# design_1_-_fan_controller.net
KiCad netlist of a schematic drawn in EAGLE
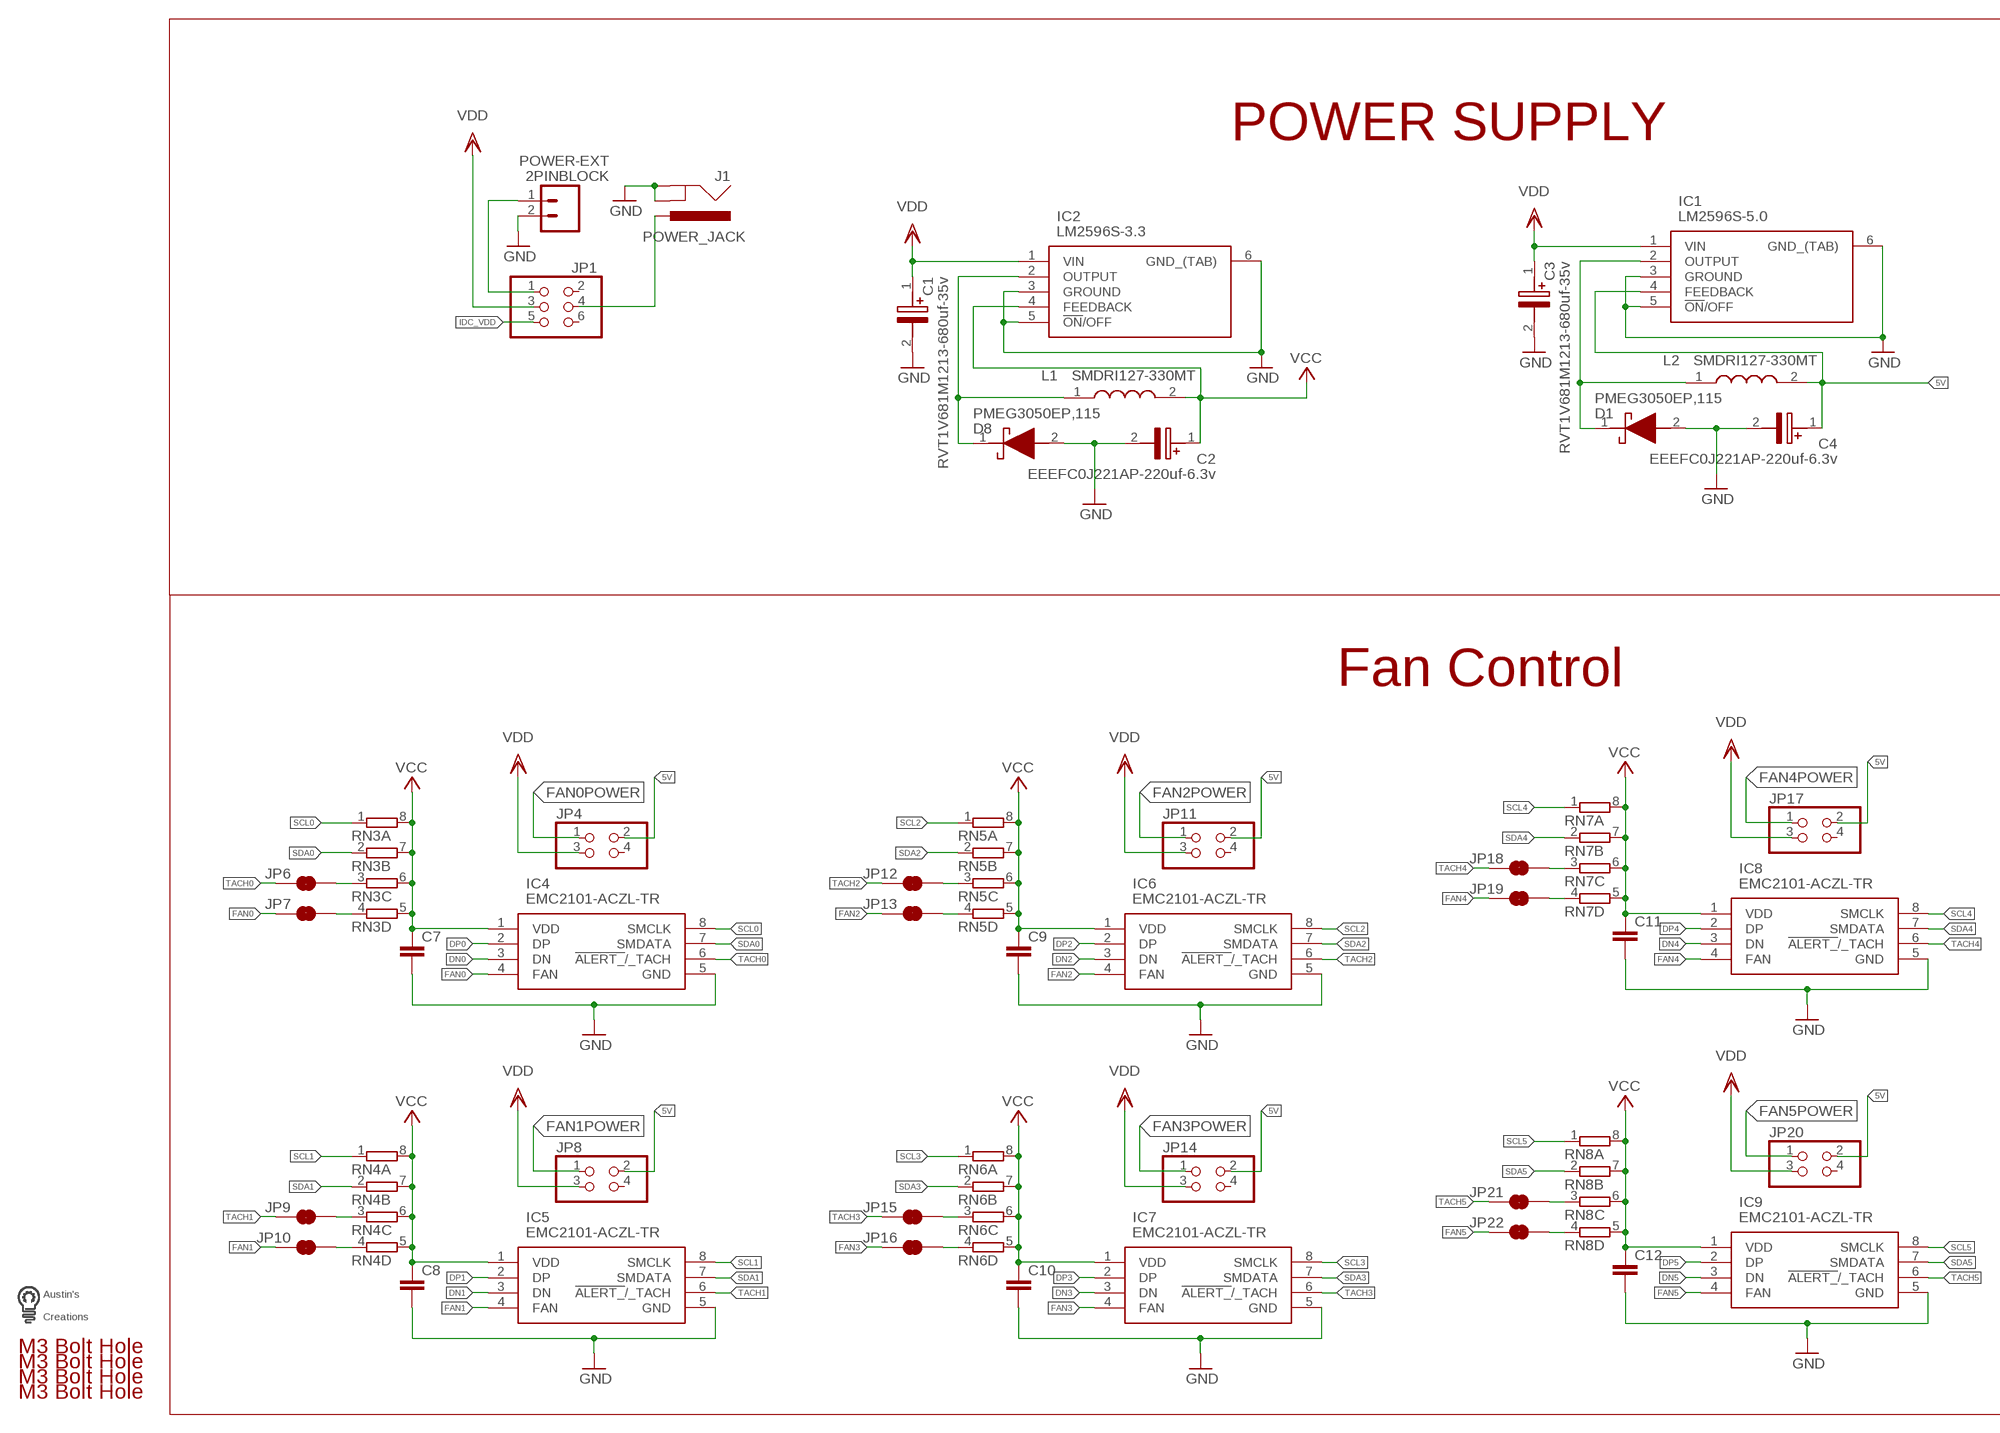
[diagram p0: schematic, sheet 1, part 1 of 2]
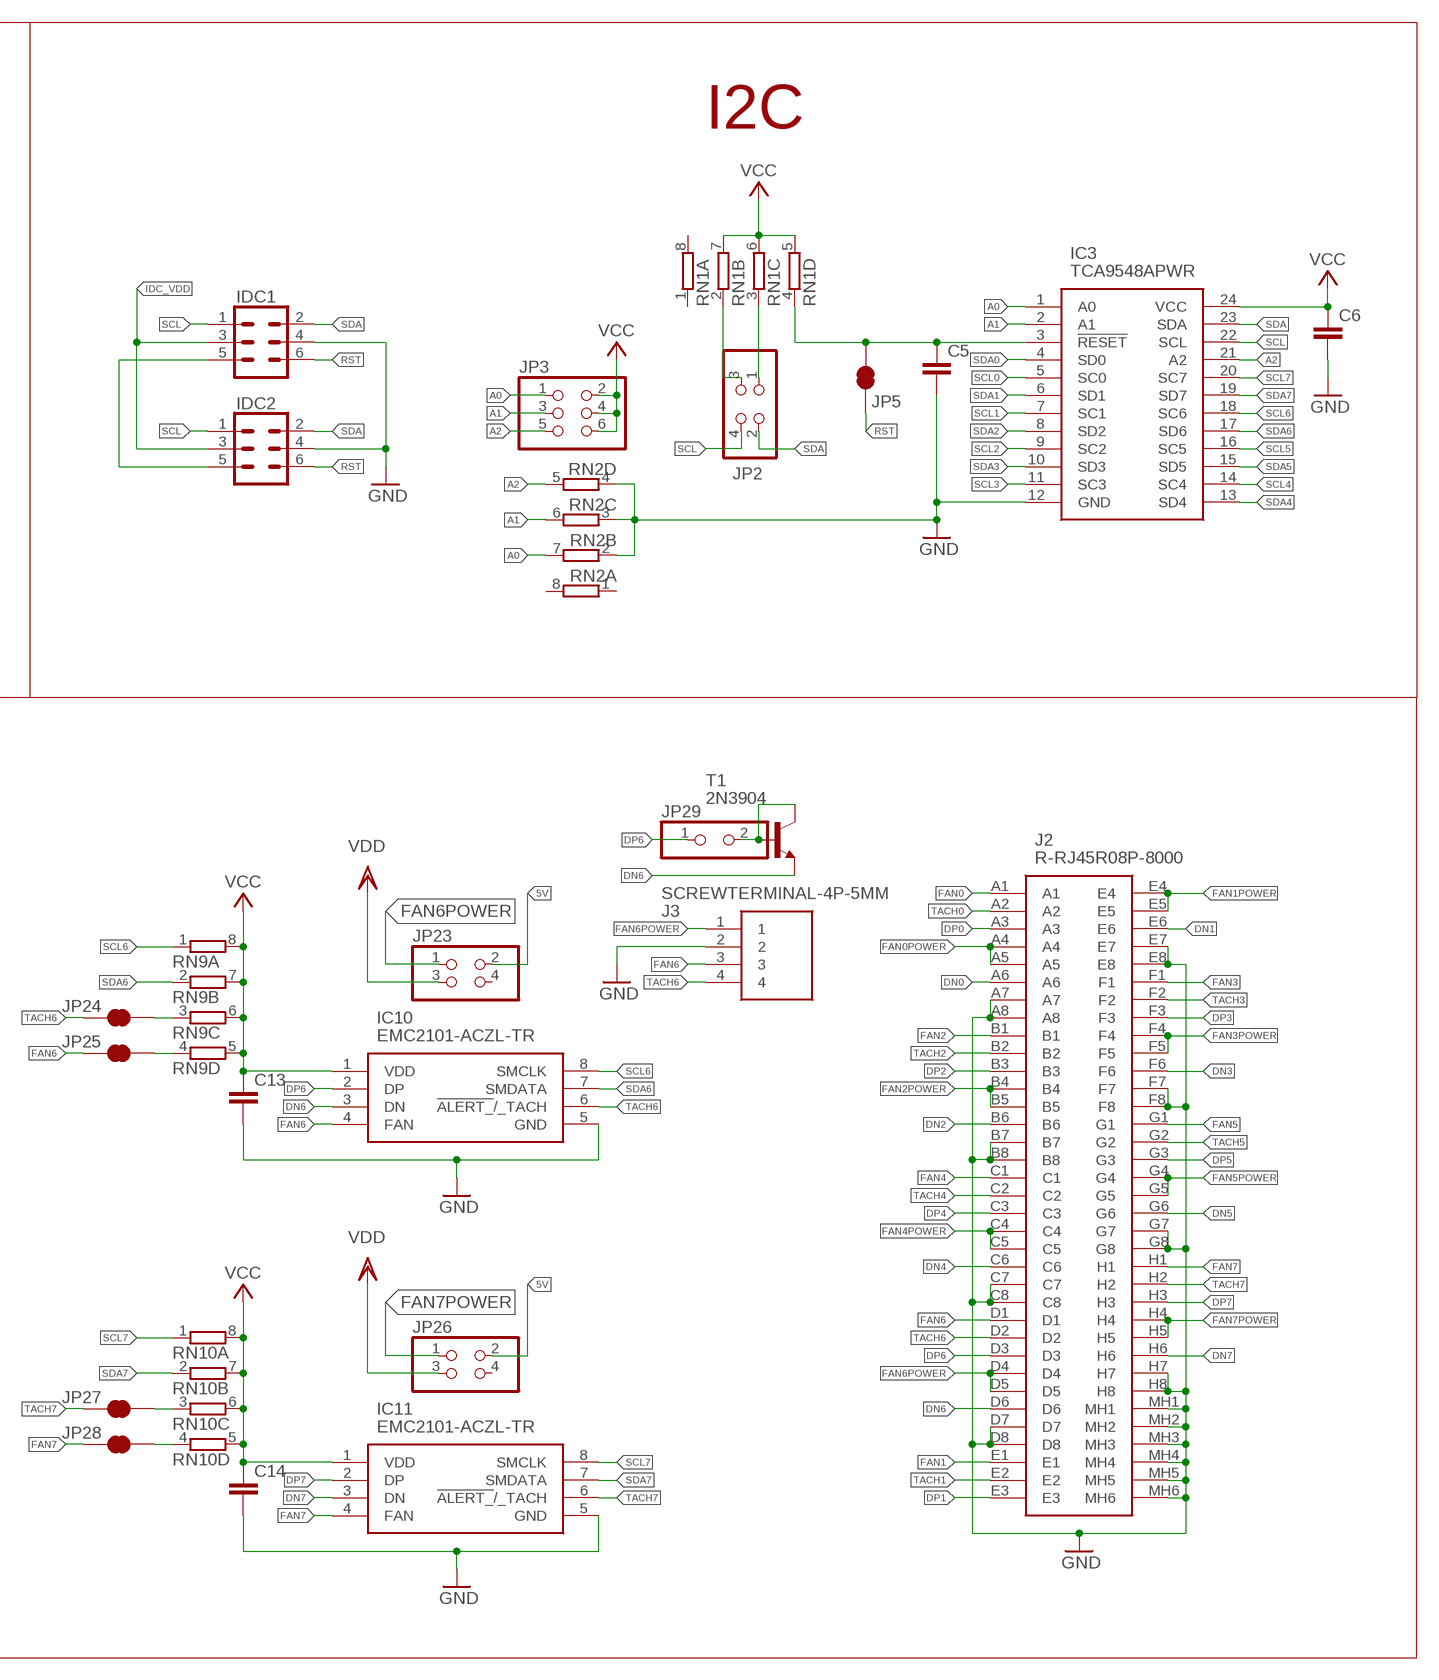
[diagram p1: schematic, sheet 1, part 2 of 2]

(export (version "E")
  (design (tool "Eeschema 10.0.6"))
  (components
    (comp (ref "C1")
      (value "RVT1V681M1213-680uf-35v")
      (footprint "eagle-import:CAPAE1350X1400N")
      (fields
        (field (name "MANUFACTURER_PART_NUMBER") "EEE-HD1V681AQ")
        (field (name "MOUSER_PART_NUMBER") "667-EEE-HD1V681AQ")
      )
      (libsource (lib "eagle-import") (part "EEE-HD1V681AQ"))
    )
    (comp (ref "C2")
      (value "EEEFC0J221AP-220uf-6.3v")
      (footprint "eagle-import:CAPAE830X650N")
      (fields (field (name "MANUFACTURER_PART_NUMBER") "EEEFC0J221AP"))
      (libsource (lib "eagle-import") (part "EEEFC0J221AP"))
    )
    (comp (ref "C3")
      (value "RVT1V681M1213-680uf-35v")
      (footprint "eagle-import:CAPAE1350X1400N")
      (fields
        (field (name "MANUFACTURER_PART_NUMBER") "EEE-HD1V681AQ")
        (field (name "MOUSER_PART_NUMBER") "667-EEE-HD1V681AQ")
      )
      (libsource (lib "eagle-import") (part "EEE-HD1V681AQ"))
    )
    (comp (ref "C4")
      (value "EEEFC0J221AP-220uf-6.3v")
      (footprint "eagle-import:CAPAE830X650N")
      (fields (field (name "MANUFACTURER_PART_NUMBER") "EEEFC0J221AP"))
      (libsource (lib "eagle-import") (part "EEEFC0J221AP"))
    )
    (comp (ref "C5")
      (value "C-EUC0603")
      (footprint "eagle-import:C0603")
      (libsource (lib "eagle-import") (part "C-EUC0603"))
    )
    (comp (ref "C6")
      (value "C-EUC0603")
      (footprint "eagle-import:C0603")
      (libsource (lib "eagle-import") (part "C-EUC0603"))
    )
    (comp (ref "C7")
      (value "C-EUC0603")
      (footprint "eagle-import:C0603")
      (libsource (lib "eagle-import") (part "C-EUC0603"))
    )
    (comp (ref "C8")
      (value "C-EUC0603")
      (footprint "eagle-import:C0603")
      (libsource (lib "eagle-import") (part "C-EUC0603"))
    )
    (comp (ref "C9")
      (value "C-EUC0603")
      (footprint "eagle-import:C0603")
      (libsource (lib "eagle-import") (part "C-EUC0603"))
    )
    (comp (ref "C10")
      (value "C-EUC0603")
      (footprint "eagle-import:C0603")
      (libsource (lib "eagle-import") (part "C-EUC0603"))
    )
    (comp (ref "C11")
      (value "C-EUC0603")
      (footprint "eagle-import:C0603")
      (libsource (lib "eagle-import") (part "C-EUC0603"))
    )
    (comp (ref "C12")
      (value "C-EUC0603")
      (footprint "eagle-import:C0603")
      (libsource (lib "eagle-import") (part "C-EUC0603"))
    )
    (comp (ref "C13")
      (value "C-EUC0603")
      (footprint "eagle-import:C0603")
      (libsource (lib "eagle-import") (part "C-EUC0603"))
    )
    (comp (ref "C14")
      (value "C-EUC0603")
      (footprint "eagle-import:C0603")
      (libsource (lib "eagle-import") (part "C-EUC0603"))
    )
    (comp (ref "D1")
      (value "PMEG3050EP,115")
      (footprint "eagle-import:PMEG3050EP115")
      (fields (field (name "MOUSER_PART_NUMBER") "771-PMEG3050EP115"))
      (libsource (lib "eagle-import") (part "PMEG3050EP,115"))
    )
    (comp (ref "D8")
      (value "PMEG3050EP,115")
      (footprint "eagle-import:PMEG3050EP115")
      (fields (field (name "MOUSER_PART_NUMBER") "771-PMEG3050EP115"))
      (libsource (lib "eagle-import") (part "PMEG3050EP,115"))
    )
    (comp (ref "IC1")
      (value "LM2596S-5.0")
      (footprint "eagle-import:TO170P1435X465-6N")
      (fields
        (field (name "MANUFACTURER_PART_NUMBER") "LM2596S-3.3/NOPB")
        (field (name "MOUSER_PART_NUMBER") "926-LM2596S-3.3/NOPB")
      )
      (libsource (lib "eagle-import") (part "LM2596S-3.3_NOPB"))
    )
    (comp (ref "IC2")
      (value "LM2596S-3.3")
      (footprint "eagle-import:TO170P1435X465-6N")
      (fields
        (field (name "MANUFACTURER_PART_NUMBER") "LM2596S-3.3/NOPB")
        (field (name "MOUSER_PART_NUMBER") "926-LM2596S-3.3/NOPB")
      )
      (libsource (lib "eagle-import") (part "LM2596S-3.3_NOPB"))
    )
    (comp (ref "IC3")
      (value "TCA9548APWR")
      (footprint "eagle-import:SOP65P640X120-24N")
      (fields (field (name "MOUSER_PART_NUMBER") "595-TCA9548APWR"))
      (libsource (lib "eagle-import") (part "TCA9548APWR"))
    )
    (comp (ref "IC4")
      (value "EMC2101-ACZL-TR")
      (footprint "eagle-import:SOP65P490X110-8N")
      (fields (field (name "MOUSER_PART_NUMBER") "886-EMC2101-ACZL-TR"))
      (libsource (lib "eagle-import") (part "EMC2101-ACZL-TR"))
    )
    (comp (ref "IC5")
      (value "EMC2101-ACZL-TR")
      (footprint "eagle-import:SOP65P490X110-8N")
      (fields (field (name "MOUSER_PART_NUMBER") "886-EMC2101-ACZL-TR"))
      (libsource (lib "eagle-import") (part "EMC2101-ACZL-TR"))
    )
    (comp (ref "IC6")
      (value "EMC2101-ACZL-TR")
      (footprint "eagle-import:SOP65P490X110-8N")
      (fields (field (name "MOUSER_PART_NUMBER") "886-EMC2101-ACZL-TR"))
      (libsource (lib "eagle-import") (part "EMC2101-ACZL-TR"))
    )
    (comp (ref "IC7")
      (value "EMC2101-ACZL-TR")
      (footprint "eagle-import:SOP65P490X110-8N")
      (fields (field (name "MOUSER_PART_NUMBER") "886-EMC2101-ACZL-TR"))
      (libsource (lib "eagle-import") (part "EMC2101-ACZL-TR"))
    )
    (comp (ref "IC8")
      (value "EMC2101-ACZL-TR")
      (footprint "eagle-import:SOP65P490X110-8N")
      (fields (field (name "MOUSER_PART_NUMBER") "886-EMC2101-ACZL-TR"))
      (libsource (lib "eagle-import") (part "EMC2101-ACZL-TR"))
    )
    (comp (ref "IC9")
      (value "EMC2101-ACZL-TR")
      (footprint "eagle-import:SOP65P490X110-8N")
      (fields (field (name "MOUSER_PART_NUMBER") "886-EMC2101-ACZL-TR"))
      (libsource (lib "eagle-import") (part "EMC2101-ACZL-TR"))
    )
    (comp (ref "IC10")
      (value "EMC2101-ACZL-TR")
      (footprint "eagle-import:SOP65P490X110-8N")
      (fields (field (name "MOUSER_PART_NUMBER") "886-EMC2101-ACZL-TR"))
      (libsource (lib "eagle-import") (part "EMC2101-ACZL-TR"))
    )
    (comp (ref "IC11")
      (value "EMC2101-ACZL-TR")
      (footprint "eagle-import:SOP65P490X110-8N")
      (fields (field (name "MOUSER_PART_NUMBER") "886-EMC2101-ACZL-TR"))
      (libsource (lib "eagle-import") (part "EMC2101-ACZL-TR"))
    )
    (comp (ref "IDC1")
      (value "CONN_03X2SHROUD")
      (footprint "eagle-import:2X3-SHROUDED")
      (libsource (lib "eagle-import") (part "CONN_03X2SHROUD"))
    )
    (comp (ref "IDC2")
      (value "CONN_03X2SHROUD")
      (footprint "eagle-import:2X3-SHROUDED")
      (libsource (lib "eagle-import") (part "CONN_03X2SHROUD"))
    )
    (comp (ref "J1")
      (value "POWER_JACK")
      (footprint "eagle-import:POWER_JACK_PTH")
      (libsource (lib "eagle-import") (part "POWER_JACK"))
    )
    (comp (ref "J2")
      (value "R-RJ45R08P-8000")
      (footprint "eagle-import:RRJ45R08P8000")
      (libsource (lib "eagle-import") (part "R-RJ45R08P-8000"))
    )
    (comp (ref "J3")
      (value "SCREWTERMINAL-4P-5MM")
      (footprint "eagle-import:SCREWTERMINAL-4P-5MM")
      (fields
        (field (name "MANUFACTURER_PART_NUMBER") "TB001-500-04BE")
        (field (name "MOUSER_PART_NUMBER") "490-TB001-500-04BE")
      )
      (libsource (lib "eagle-import") (part "SCREWTERMINAL-4P-5MM"))
    )
    (comp (ref "JP1")
      (value "PINHD-2X3")
      (footprint "eagle-import:2X03")
      (libsource (lib "eagle-import") (part "PINHD-2X3"))
    )
    (comp (ref "JP2")
      (value "PINHD-2X2")
      (footprint "eagle-import:2X02")
      (libsource (lib "eagle-import") (part "PINHD-2X2"))
    )
    (comp (ref "JP3")
      (value "PINHD-2X3")
      (footprint "eagle-import:2X03")
      (libsource (lib "eagle-import") (part "PINHD-2X3"))
    )
    (comp (ref "JP4")
      (value "PINHD-2X2")
      (footprint "eagle-import:2X02")
      (libsource (lib "eagle-import") (part "PINHD-2X2"))
    )
    (comp (ref "JP5")
      (value "JUMPER-SMT_2_NC_TRACE_SILK")
      (footprint "eagle-import:SMT-JUMPER_2_NC_TRACE_SILK")
      (libsource (lib "eagle-import") (part "JUMPER-SMT_2_NC_TRACE_SILK"))
    )
    (comp (ref "JP6")
      (value "JUMPER-SMT_2_NC_TRACE_SILK")
      (footprint "eagle-import:SMT-JUMPER_2_NC_TRACE_SILK")
      (libsource (lib "eagle-import") (part "JUMPER-SMT_2_NC_TRACE_SILK"))
    )
    (comp (ref "JP7")
      (value "JUMPER-SMT_2_NC_TRACE_SILK")
      (footprint "eagle-import:SMT-JUMPER_2_NC_TRACE_SILK")
      (libsource (lib "eagle-import") (part "JUMPER-SMT_2_NC_TRACE_SILK"))
    )
    (comp (ref "JP8")
      (value "PINHD-2X2")
      (footprint "eagle-import:2X02")
      (libsource (lib "eagle-import") (part "PINHD-2X2"))
    )
    (comp (ref "JP9")
      (value "JUMPER-SMT_2_NC_TRACE_SILK")
      (footprint "eagle-import:SMT-JUMPER_2_NC_TRACE_SILK")
      (libsource (lib "eagle-import") (part "JUMPER-SMT_2_NC_TRACE_SILK"))
    )
    (comp (ref "JP10")
      (value "JUMPER-SMT_2_NC_TRACE_SILK")
      (footprint "eagle-import:SMT-JUMPER_2_NC_TRACE_SILK")
      (libsource (lib "eagle-import") (part "JUMPER-SMT_2_NC_TRACE_SILK"))
    )
    (comp (ref "JP11")
      (value "PINHD-2X2")
      (footprint "eagle-import:2X02")
      (libsource (lib "eagle-import") (part "PINHD-2X2"))
    )
    (comp (ref "JP12")
      (value "JUMPER-SMT_2_NC_TRACE_SILK")
      (footprint "eagle-import:SMT-JUMPER_2_NC_TRACE_SILK")
      (libsource (lib "eagle-import") (part "JUMPER-SMT_2_NC_TRACE_SILK"))
    )
    (comp (ref "JP13")
      (value "JUMPER-SMT_2_NC_TRACE_SILK")
      (footprint "eagle-import:SMT-JUMPER_2_NC_TRACE_SILK")
      (libsource (lib "eagle-import") (part "JUMPER-SMT_2_NC_TRACE_SILK"))
    )
    (comp (ref "JP14")
      (value "PINHD-2X2")
      (footprint "eagle-import:2X02")
      (libsource (lib "eagle-import") (part "PINHD-2X2"))
    )
    (comp (ref "JP15")
      (value "JUMPER-SMT_2_NC_TRACE_SILK")
      (footprint "eagle-import:SMT-JUMPER_2_NC_TRACE_SILK")
      (libsource (lib "eagle-import") (part "JUMPER-SMT_2_NC_TRACE_SILK"))
    )
    (comp (ref "JP16")
      (value "JUMPER-SMT_2_NC_TRACE_SILK")
      (footprint "eagle-import:SMT-JUMPER_2_NC_TRACE_SILK")
      (libsource (lib "eagle-import") (part "JUMPER-SMT_2_NC_TRACE_SILK"))
    )
    (comp (ref "JP17")
      (value "PINHD-2X2")
      (footprint "eagle-import:2X02")
      (libsource (lib "eagle-import") (part "PINHD-2X2"))
    )
    (comp (ref "JP18")
      (value "JUMPER-SMT_2_NC_TRACE_SILK")
      (footprint "eagle-import:SMT-JUMPER_2_NC_TRACE_SILK")
      (libsource (lib "eagle-import") (part "JUMPER-SMT_2_NC_TRACE_SILK"))
    )
    (comp (ref "JP19")
      (value "JUMPER-SMT_2_NC_TRACE_SILK")
      (footprint "eagle-import:SMT-JUMPER_2_NC_TRACE_SILK")
      (libsource (lib "eagle-import") (part "JUMPER-SMT_2_NC_TRACE_SILK"))
    )
    (comp (ref "JP20")
      (value "PINHD-2X2")
      (footprint "eagle-import:2X02")
      (libsource (lib "eagle-import") (part "PINHD-2X2"))
    )
    (comp (ref "JP21")
      (value "JUMPER-SMT_2_NC_TRACE_SILK")
      (footprint "eagle-import:SMT-JUMPER_2_NC_TRACE_SILK")
      (libsource (lib "eagle-import") (part "JUMPER-SMT_2_NC_TRACE_SILK"))
    )
    (comp (ref "JP22")
      (value "JUMPER-SMT_2_NC_TRACE_SILK")
      (footprint "eagle-import:SMT-JUMPER_2_NC_TRACE_SILK")
      (libsource (lib "eagle-import") (part "JUMPER-SMT_2_NC_TRACE_SILK"))
    )
    (comp (ref "JP23")
      (value "PINHD-2X2")
      (footprint "eagle-import:2X02")
      (libsource (lib "eagle-import") (part "PINHD-2X2"))
    )
    (comp (ref "JP24")
      (value "JUMPER-SMT_2_NC_TRACE_SILK")
      (footprint "eagle-import:SMT-JUMPER_2_NC_TRACE_SILK")
      (libsource (lib "eagle-import") (part "JUMPER-SMT_2_NC_TRACE_SILK"))
    )
    (comp (ref "JP25")
      (value "JUMPER-SMT_2_NC_TRACE_SILK")
      (footprint "eagle-import:SMT-JUMPER_2_NC_TRACE_SILK")
      (libsource (lib "eagle-import") (part "JUMPER-SMT_2_NC_TRACE_SILK"))
    )
    (comp (ref "JP26")
      (value "PINHD-2X2")
      (footprint "eagle-import:2X02")
      (libsource (lib "eagle-import") (part "PINHD-2X2"))
    )
    (comp (ref "JP27")
      (value "JUMPER-SMT_2_NC_TRACE_SILK")
      (footprint "eagle-import:SMT-JUMPER_2_NC_TRACE_SILK")
      (libsource (lib "eagle-import") (part "JUMPER-SMT_2_NC_TRACE_SILK"))
    )
    (comp (ref "JP28")
      (value "JUMPER-SMT_2_NC_TRACE_SILK")
      (footprint "eagle-import:SMT-JUMPER_2_NC_TRACE_SILK")
      (libsource (lib "eagle-import") (part "JUMPER-SMT_2_NC_TRACE_SILK"))
    )
    (comp (ref "JP29")
      (value "PINHD-1X2")
      (footprint "eagle-import:1X02")
      (libsource (lib "eagle-import") (part "PINHD-1X2"))
    )
    (comp (ref "L1")
      (value "SMDRI127-330MT")
      (footprint "eagle-import:INDPM120120X800N")
      (fields
        (field (name "MANUFACTURER_PART_NUMBER") "CDRH127/LDNP-330MC")
        (field (name "MOUSER_PART_NUMBER") "851-CDRH127LDNP330MC")
      )
      (libsource (lib "eagle-import") (part "CDRH127_LDNP-330MC"))
    )
    (comp (ref "L2")
      (value "SMDRI127-330MT")
      (footprint "eagle-import:INDPM120120X800N")
      (fields
        (field (name "MANUFACTURER_PART_NUMBER") "CDRH127/LDNP-330MC")
        (field (name "MOUSER_PART_NUMBER") "851-CDRH127LDNP330MC")
      )
      (libsource (lib "eagle-import") (part "CDRH127_LDNP-330MC"))
    )
    (comp (ref "POWER-EXT")
      (value "2PINBLOCK")
      (footprint "eagle-import:SCREWTERMINAL-5MM-2")
      (libsource (lib "eagle-import") (part "2PINBLOCK"))
    )
    (comp (ref "RN1")
      (value "4R-N0603-ARC")
      (footprint "eagle-import:0603-ARC")
      (libsource (lib "eagle-import") (part "4R-N0603-ARC"))
    )
    (comp (ref "RN2")
      (value "4R-N0603-ARC")
      (footprint "eagle-import:0603-ARC")
      (libsource (lib "eagle-import") (part "4R-N0603-ARC"))
    )
    (comp (ref "RN3")
      (value "4R-N0603-ARC")
      (footprint "eagle-import:0603-ARC")
      (libsource (lib "eagle-import") (part "4R-N0603-ARC"))
    )
    (comp (ref "RN4")
      (value "4R-N0603-ARC")
      (footprint "eagle-import:0603-ARC")
      (libsource (lib "eagle-import") (part "4R-N0603-ARC"))
    )
    (comp (ref "RN5")
      (value "4R-N0603-ARC")
      (footprint "eagle-import:0603-ARC")
      (libsource (lib "eagle-import") (part "4R-N0603-ARC"))
    )
    (comp (ref "RN6")
      (value "4R-N0603-ARC")
      (footprint "eagle-import:0603-ARC")
      (libsource (lib "eagle-import") (part "4R-N0603-ARC"))
    )
    (comp (ref "RN7")
      (value "4R-N0603-ARC")
      (footprint "eagle-import:0603-ARC")
      (libsource (lib "eagle-import") (part "4R-N0603-ARC"))
    )
    (comp (ref "RN8")
      (value "4R-N0603-ARC")
      (footprint "eagle-import:0603-ARC")
      (libsource (lib "eagle-import") (part "4R-N0603-ARC"))
    )
    (comp (ref "RN9")
      (value "4R-N0603-ARC")
      (footprint "eagle-import:0603-ARC")
      (libsource (lib "eagle-import") (part "4R-N0603-ARC"))
    )
    (comp (ref "RN10")
      (value "4R-N0603-ARC")
      (footprint "eagle-import:0603-ARC")
      (libsource (lib "eagle-import") (part "4R-N0603-ARC"))
    )
    (comp (ref "T1")
      (value "2N3904")
      (footprint "eagle-import:TO92")
      (libsource (lib "eagle-import") (part "2N3904"))
    )
    (comp (ref "U$1")
      (value "M3BOLTHOLE")
      (footprint "eagle-import:M3BOLTHOLE")
      (libsource (lib "eagle-import") (part "M3BOLTHOLE"))
    )
    (comp (ref "U$2")
      (value "M3BOLTHOLE")
      (footprint "eagle-import:M3BOLTHOLE")
      (libsource (lib "eagle-import") (part "M3BOLTHOLE"))
    )
    (comp (ref "U$3")
      (value "M3BOLTHOLE")
      (footprint "eagle-import:M3BOLTHOLE")
      (libsource (lib "eagle-import") (part "M3BOLTHOLE"))
    )
    (comp (ref "U$4")
      (value "M3BOLTHOLE")
      (footprint "eagle-import:M3BOLTHOLE")
      (libsource (lib "eagle-import") (part "M3BOLTHOLE"))
    )
    (comp (ref "U$5")
      (value "LOGOMED")
      (footprint "eagle-import:LOGOMED")
      (libsource (lib "eagle-import") (part "LOGOMED"))
    )
  )
  (nets
    (net (code "1") (name "5V") (class "Default")
      (node (ref "C4") (pin "1") (pinfunction "+_1") (pintype "bidirectional"))
      (node (ref "IC1") (pin "4") (pinfunction "FEEDBACK_4") (pintype "bidirectional"))
      (node (ref "JP11") (pin "2") (pinfunction "2_2") (pintype "passive"))
      (node (ref "JP14") (pin "2") (pinfunction "2_2") (pintype "passive"))
      (node (ref "JP17") (pin "2") (pinfunction "2_2") (pintype "passive"))
      (node (ref "JP20") (pin "2") (pinfunction "2_2") (pintype "passive"))
      (node (ref "JP23") (pin "2") (pinfunction "2_2") (pintype "passive"))
      (node (ref "JP26") (pin "2") (pinfunction "2_2") (pintype "passive"))
      (node (ref "JP4") (pin "2") (pinfunction "2_2") (pintype "passive"))
      (node (ref "JP8") (pin "2") (pinfunction "2_2") (pintype "passive"))
      (node (ref "L2") (pin "2") (pinfunction "2_2") (pintype "bidirectional"))
    )
    (net (code "2") (name "A0") (class "Default")
      (node (ref "IC3") (pin "1") (pinfunction "A0_1") (pintype "bidirectional"))
      (node (ref "JP3") (pin "1") (pinfunction "1_1") (pintype "passive"))
      (node (ref "RN2") (pin "7") (pinfunction "2_7") (pintype "passive"))
    )
    (net (code "3") (name "A1") (class "Default")
      (node (ref "IC3") (pin "2") (pinfunction "A1_2") (pintype "bidirectional"))
      (node (ref "JP3") (pin "3") (pinfunction "3_3") (pintype "passive"))
      (node (ref "RN2") (pin "6") (pinfunction "2_6") (pintype "passive"))
    )
    (net (code "4") (name "A2") (class "Default")
      (node (ref "IC3") (pin "21") (pinfunction "A2_21") (pintype "bidirectional"))
      (node (ref "JP3") (pin "5") (pinfunction "5_5") (pintype "passive"))
      (node (ref "RN2") (pin "5") (pinfunction "2_5") (pintype "passive"))
    )
    (net (code "5") (name "DN0") (class "Default")
      (node (ref "IC4") (pin "3") (pinfunction "DN_3") (pintype "input"))
      (node (ref "J2") (pin "A6") (pinfunction "A6_A6") (pintype "bidirectional"))
    )
    (net (code "6") (name "DN1") (class "Default")
      (node (ref "IC5") (pin "3") (pinfunction "DN_3") (pintype "input"))
      (node (ref "J2") (pin "E6") (pinfunction "E6_E6") (pintype "bidirectional"))
    )
    (net (code "7") (name "DN2") (class "Default")
      (node (ref "IC6") (pin "3") (pinfunction "DN_3") (pintype "input"))
      (node (ref "J2") (pin "B6") (pinfunction "B6_B6") (pintype "bidirectional"))
    )
    (net (code "8") (name "DN3") (class "Default")
      (node (ref "IC7") (pin "3") (pinfunction "DN_3") (pintype "input"))
      (node (ref "J2") (pin "F6") (pinfunction "F6_F6") (pintype "bidirectional"))
    )
    (net (code "9") (name "DN4") (class "Default")
      (node (ref "IC8") (pin "3") (pinfunction "DN_3") (pintype "input"))
      (node (ref "J2") (pin "C6") (pinfunction "C6_C6") (pintype "bidirectional"))
    )
    (net (code "10") (name "DN5") (class "Default")
      (node (ref "IC9") (pin "3") (pinfunction "DN_3") (pintype "input"))
      (node (ref "J2") (pin "G6") (pinfunction "G6_G6") (pintype "bidirectional"))
    )
    (net (code "11") (name "DN6") (class "Default")
      (node (ref "IC10") (pin "3") (pinfunction "DN_3") (pintype "input"))
      (node (ref "J2") (pin "D6") (pinfunction "D6_D6") (pintype "bidirectional"))
      (node (ref "T1") (pin "3") (pinfunction "E_3") (pintype "passive"))
    )
    (net (code "12") (name "DN7") (class "Default")
      (node (ref "IC11") (pin "3") (pinfunction "DN_3") (pintype "input"))
      (node (ref "J2") (pin "H6") (pinfunction "H6_H6") (pintype "bidirectional"))
    )
    (net (code "13") (name "DP0") (class "Default")
      (node (ref "IC4") (pin "2") (pinfunction "DP_2") (pintype "input"))
      (node (ref "J2") (pin "A3") (pinfunction "A3_A3") (pintype "bidirectional"))
    )
    (net (code "14") (name "DP1") (class "Default")
      (node (ref "IC5") (pin "2") (pinfunction "DP_2") (pintype "input"))
      (node (ref "J2") (pin "E3") (pinfunction "E3_E3") (pintype "bidirectional"))
    )
    (net (code "15") (name "DP2") (class "Default")
      (node (ref "IC6") (pin "2") (pinfunction "DP_2") (pintype "input"))
      (node (ref "J2") (pin "B3") (pinfunction "B3_B3") (pintype "bidirectional"))
    )
    (net (code "16") (name "DP3") (class "Default")
      (node (ref "IC7") (pin "2") (pinfunction "DP_2") (pintype "input"))
      (node (ref "J2") (pin "F3") (pinfunction "F3_F3") (pintype "bidirectional"))
    )
    (net (code "17") (name "DP4") (class "Default")
      (node (ref "IC8") (pin "2") (pinfunction "DP_2") (pintype "input"))
      (node (ref "J2") (pin "C3") (pinfunction "C3_C3") (pintype "bidirectional"))
    )
    (net (code "18") (name "DP5") (class "Default")
      (node (ref "IC9") (pin "2") (pinfunction "DP_2") (pintype "input"))
      (node (ref "J2") (pin "G3") (pinfunction "G3_G3") (pintype "bidirectional"))
    )
    (net (code "19") (name "DP6") (class "Default")
      (node (ref "IC10") (pin "2") (pinfunction "DP_2") (pintype "input"))
      (node (ref "J2") (pin "D3") (pinfunction "D3_D3") (pintype "bidirectional"))
      (node (ref "JP29") (pin "1") (pinfunction "1_1") (pintype "passive"))
    )
    (net (code "20") (name "DP7") (class "Default")
      (node (ref "IC11") (pin "2") (pinfunction "DP_2") (pintype "input"))
      (node (ref "J2") (pin "H3") (pinfunction "H3_H3") (pintype "bidirectional"))
    )
    (net (code "21") (name "FAN0") (class "Default")
      (node (ref "IC4") (pin "4") (pinfunction "FAN_4") (pintype "output"))
      (node (ref "J2") (pin "A1") (pinfunction "A1_A1") (pintype "bidirectional"))
      (node (ref "JP7") (pin "1") (pinfunction "1_1") (pintype "passive"))
    )
    (net (code "22") (name "FAN0POWER") (class "Default")
      (node (ref "J2") (pin "A4") (pinfunction "A4_A4") (pintype "bidirectional"))
      (node (ref "J2") (pin "A5") (pinfunction "A5_A5") (pintype "bidirectional"))
      (node (ref "JP4") (pin "1") (pinfunction "1_1") (pintype "passive"))
    )
    (net (code "23") (name "FAN1") (class "Default")
      (node (ref "IC5") (pin "4") (pinfunction "FAN_4") (pintype "output"))
      (node (ref "J2") (pin "E1") (pinfunction "E1_E1") (pintype "bidirectional"))
      (node (ref "JP10") (pin "1") (pinfunction "1_1") (pintype "passive"))
    )
    (net (code "24") (name "FAN1POWER") (class "Default")
      (node (ref "J2") (pin "E4") (pinfunction "E4_E4") (pintype "bidirectional"))
      (node (ref "J2") (pin "E5") (pinfunction "E5_E5") (pintype "bidirectional"))
      (node (ref "JP8") (pin "1") (pinfunction "1_1") (pintype "passive"))
    )
    (net (code "25") (name "FAN2") (class "Default")
      (node (ref "IC6") (pin "4") (pinfunction "FAN_4") (pintype "output"))
      (node (ref "J2") (pin "B1") (pinfunction "B1_B1") (pintype "bidirectional"))
      (node (ref "JP13") (pin "1") (pinfunction "1_1") (pintype "passive"))
    )
    (net (code "26") (name "FAN2POWER") (class "Default")
      (node (ref "J2") (pin "B4") (pinfunction "B4_B4") (pintype "bidirectional"))
      (node (ref "J2") (pin "B5") (pinfunction "B5_B5") (pintype "bidirectional"))
      (node (ref "JP11") (pin "1") (pinfunction "1_1") (pintype "passive"))
    )
    (net (code "27") (name "FAN3") (class "Default")
      (node (ref "IC7") (pin "4") (pinfunction "FAN_4") (pintype "output"))
      (node (ref "J2") (pin "F1") (pinfunction "F1_F1") (pintype "bidirectional"))
      (node (ref "JP16") (pin "1") (pinfunction "1_1") (pintype "passive"))
    )
    (net (code "28") (name "FAN3POWER") (class "Default")
      (node (ref "J2") (pin "F4") (pinfunction "F4_F4") (pintype "bidirectional"))
      (node (ref "J2") (pin "F5") (pinfunction "F5_F5") (pintype "bidirectional"))
      (node (ref "JP14") (pin "1") (pinfunction "1_1") (pintype "passive"))
    )
    (net (code "29") (name "FAN4") (class "Default")
      (node (ref "IC8") (pin "4") (pinfunction "FAN_4") (pintype "output"))
      (node (ref "J2") (pin "C1") (pinfunction "C1_C1") (pintype "bidirectional"))
      (node (ref "JP19") (pin "1") (pinfunction "1_1") (pintype "passive"))
    )
    (net (code "30") (name "FAN4POWER") (class "Default")
      (node (ref "J2") (pin "C4") (pinfunction "C4_C4") (pintype "bidirectional"))
      (node (ref "J2") (pin "C5") (pinfunction "C5_C5") (pintype "bidirectional"))
      (node (ref "JP17") (pin "1") (pinfunction "1_1") (pintype "passive"))
    )
    (net (code "31") (name "FAN5") (class "Default")
      (node (ref "IC9") (pin "4") (pinfunction "FAN_4") (pintype "output"))
      (node (ref "J2") (pin "G1") (pinfunction "G1_G1") (pintype "bidirectional"))
      (node (ref "JP22") (pin "1") (pinfunction "1_1") (pintype "passive"))
    )
    (net (code "32") (name "FAN5POWER") (class "Default")
      (node (ref "J2") (pin "G4") (pinfunction "G4_G4") (pintype "bidirectional"))
      (node (ref "J2") (pin "G5") (pinfunction "G5_G5") (pintype "bidirectional"))
      (node (ref "JP20") (pin "1") (pinfunction "1_1") (pintype "passive"))
    )
    (net (code "33") (name "FAN6") (class "Default")
      (node (ref "IC10") (pin "4") (pinfunction "FAN_4") (pintype "output"))
      (node (ref "J2") (pin "D1") (pinfunction "D1_D1") (pintype "bidirectional"))
      (node (ref "J3") (pin "3") (pinfunction "3_3") (pintype "bidirectional"))
      (node (ref "JP25") (pin "1") (pinfunction "1_1") (pintype "passive"))
    )
    (net (code "34") (name "FAN6POWER") (class "Default")
      (node (ref "J2") (pin "D4") (pinfunction "D4_D4") (pintype "bidirectional"))
      (node (ref "J2") (pin "D5") (pinfunction "D5_D5") (pintype "bidirectional"))
      (node (ref "J3") (pin "1") (pinfunction "1_1") (pintype "bidirectional"))
      (node (ref "JP23") (pin "1") (pinfunction "1_1") (pintype "passive"))
    )
    (net (code "35") (name "FAN7") (class "Default")
      (node (ref "IC11") (pin "4") (pinfunction "FAN_4") (pintype "output"))
      (node (ref "J2") (pin "H1") (pinfunction "H1_H1") (pintype "bidirectional"))
      (node (ref "JP28") (pin "1") (pinfunction "1_1") (pintype "passive"))
    )
    (net (code "36") (name "FAN7POWER") (class "Default")
      (node (ref "J2") (pin "H4") (pinfunction "H4_H4") (pintype "bidirectional"))
      (node (ref "J2") (pin "H5") (pinfunction "H5_H5") (pintype "bidirectional"))
      (node (ref "JP26") (pin "1") (pinfunction "1_1") (pintype "passive"))
    )
    (net (code "37") (name "GND") (class "Default")
      (node (ref "C1") (pin "2") (pinfunction "-_2") (pintype "bidirectional"))
      (node (ref "C10") (pin "2") (pinfunction "2_2") (pintype "passive"))
      (node (ref "C11") (pin "2") (pinfunction "2_2") (pintype "passive"))
      (node (ref "C12") (pin "2") (pinfunction "2_2") (pintype "passive"))
      (node (ref "C13") (pin "2") (pinfunction "2_2") (pintype "passive"))
      (node (ref "C14") (pin "2") (pinfunction "2_2") (pintype "passive"))
      (node (ref "C2") (pin "2") (pinfunction "-_2") (pintype "bidirectional"))
      (node (ref "C3") (pin "2") (pinfunction "-_2") (pintype "bidirectional"))
      (node (ref "C4") (pin "2") (pinfunction "-_2") (pintype "bidirectional"))
      (node (ref "C5") (pin "2") (pinfunction "2_2") (pintype "passive"))
      (node (ref "C6") (pin "2") (pinfunction "2_2") (pintype "passive"))
      (node (ref "C7") (pin "2") (pinfunction "2_2") (pintype "passive"))
      (node (ref "C8") (pin "2") (pinfunction "2_2") (pintype "passive"))
      (node (ref "C9") (pin "2") (pinfunction "2_2") (pintype "passive"))
      (node (ref "D1") (pin "2") (pinfunction "A_2") (pintype "bidirectional"))
      (node (ref "D8") (pin "2") (pinfunction "A_2") (pintype "bidirectional"))
      (node (ref "IC1") (pin "3") (pinfunction "GROUND_3") (pintype "bidirectional"))
      (node (ref "IC1") (pin "5") (pinfunction "~{ON}/OFF_5") (pintype "bidirectional"))
      (node (ref "IC1") (pin "6") (pinfunction "GND_(TAB)_6") (pintype "power_in"))
      (node (ref "IC10") (pin "5") (pinfunction "GND_5") (pintype "power_in"))
      (node (ref "IC11") (pin "5") (pinfunction "GND_5") (pintype "power_in"))
      (node (ref "IC2") (pin "3") (pinfunction "GROUND_3") (pintype "bidirectional"))
      (node (ref "IC2") (pin "5") (pinfunction "~{ON}/OFF_5") (pintype "bidirectional"))
      (node (ref "IC2") (pin "6") (pinfunction "GND_(TAB)_6") (pintype "power_in"))
      (node (ref "IC3") (pin "12") (pinfunction "GND_12") (pintype "bidirectional"))
      (node (ref "IC4") (pin "5") (pinfunction "GND_5") (pintype "power_in"))
      (node (ref "IC5") (pin "5") (pinfunction "GND_5") (pintype "power_in"))
      (node (ref "IC6") (pin "5") (pinfunction "GND_5") (pintype "power_in"))
      (node (ref "IC7") (pin "5") (pinfunction "GND_5") (pintype "power_in"))
      (node (ref "IC8") (pin "5") (pinfunction "GND_5") (pintype "power_in"))
      (node (ref "IC9") (pin "5") (pinfunction "GND_5") (pintype "power_in"))
      (node (ref "IDC1") (pin "4") (pinfunction "4_4") (pintype "bidirectional"))
      (node (ref "IDC2") (pin "4") (pinfunction "4_4") (pintype "bidirectional"))
      (node (ref "J1") (pin "GND") (pinfunction "GND_GND") (pintype "bidirectional"))
      (node (ref "J1") (pin "GNDBREAK") (pinfunction "GNDBREAK_GNDBREAK") (pintype "bidirectional"))
      (node (ref "J2") (pin "A7") (pinfunction "A7_A7") (pintype "bidirectional"))
      (node (ref "J2") (pin "A8") (pinfunction "A8_A8") (pintype "bidirectional"))
      (node (ref "J2") (pin "B7") (pinfunction "B7_B7") (pintype "bidirectional"))
      (node (ref "J2") (pin "B8") (pinfunction "B8_B8") (pintype "bidirectional"))
      (node (ref "J2") (pin "C7") (pinfunction "C7_C7") (pintype "bidirectional"))
      (node (ref "J2") (pin "C8") (pinfunction "C8_C8") (pintype "bidirectional"))
      (node (ref "J2") (pin "D7") (pinfunction "D7_D7") (pintype "bidirectional"))
      (node (ref "J2") (pin "D8") (pinfunction "D8_D8") (pintype "bidirectional"))
      (node (ref "J2") (pin "E7") (pinfunction "E7_E7") (pintype "bidirectional"))
      (node (ref "J2") (pin "E8") (pinfunction "E8_E8") (pintype "bidirectional"))
      (node (ref "J2") (pin "F7") (pinfunction "F7_F7") (pintype "bidirectional"))
      (node (ref "J2") (pin "F8") (pinfunction "F8_F8") (pintype "bidirectional"))
      (node (ref "J2") (pin "G7") (pinfunction "G7_G7") (pintype "bidirectional"))
      (node (ref "J2") (pin "G8") (pinfunction "G8_G8") (pintype "bidirectional"))
      (node (ref "J2") (pin "H7") (pinfunction "H7_H7") (pintype "bidirectional"))
      (node (ref "J2") (pin "H8") (pinfunction "H8_H8") (pintype "bidirectional"))
      (node (ref "J2") (pin "MH1") (pinfunction "MH1_MH1") (pintype "bidirectional"))
      (node (ref "J2") (pin "MH2") (pinfunction "MH2_MH2") (pintype "bidirectional"))
      (node (ref "J2") (pin "MH3") (pinfunction "MH3_MH3") (pintype "bidirectional"))
      (node (ref "J2") (pin "MH4") (pinfunction "MH4_MH4") (pintype "bidirectional"))
      (node (ref "J2") (pin "MH5") (pinfunction "MH5_MH5") (pintype "bidirectional"))
      (node (ref "J2") (pin "MH6") (pinfunction "MH6_MH6") (pintype "bidirectional"))
      (node (ref "J3") (pin "2") (pinfunction "2_2") (pintype "bidirectional"))
      (node (ref "POWER-EXT") (pin "2") (pinfunction "2_2") (pintype "passive"))
      (node (ref "RN2") (pin "2") (pinfunction "1_2") (pintype "passive"))
      (node (ref "RN2") (pin "3") (pinfunction "1_3") (pintype "passive"))
      (node (ref "RN2") (pin "4") (pinfunction "1_4") (pintype "passive"))
    )
    (net (code "38") (name "IDC_VDD") (class "Default")
      (node (ref "IDC1") (pin "3") (pinfunction "3_3") (pintype "bidirectional"))
      (node (ref "IDC2") (pin "3") (pinfunction "3_3") (pintype "bidirectional"))
      (node (ref "JP1") (pin "5") (pinfunction "5_5") (pintype "passive"))
    )
    (net (code "39") (name "Net-(D1-K)") (class "Default")
      (node (ref "D1") (pin "1") (pinfunction "K_1") (pintype "bidirectional"))
      (node (ref "IC1") (pin "2") (pinfunction "OUTPUT_2") (pintype "output"))
      (node (ref "L2") (pin "1") (pinfunction "1_1") (pintype "bidirectional"))
    )
    (net (code "40") (name "Net-(D8-K)") (class "Default")
      (node (ref "D8") (pin "1") (pinfunction "K_1") (pintype "bidirectional"))
      (node (ref "IC2") (pin "2") (pinfunction "OUTPUT_2") (pintype "output"))
      (node (ref "L1") (pin "1") (pinfunction "1_1") (pintype "bidirectional"))
    )
    (net (code "41") (name "Net-(IC3-~{RESET})") (class "Default")
      (node (ref "C5") (pin "1") (pinfunction "1_1") (pintype "passive"))
      (node (ref "IC3") (pin "3") (pinfunction "~{RESET}_3") (pintype "bidirectional"))
      (node (ref "JP5") (pin "2") (pinfunction "2_2") (pintype "passive"))
      (node (ref "RN1") (pin "4") (pinfunction "1_4") (pintype "passive"))
    )
    (net (code "42") (name "Net-(IDC1-Pad5)") (class "Default")
      (node (ref "IDC1") (pin "5") (pinfunction "5_5") (pintype "bidirectional"))
      (node (ref "IDC2") (pin "5") (pinfunction "5_5") (pintype "bidirectional"))
    )
    (net (code "43") (name "Net-(J1-PadPWR)") (class "Default")
      (node (ref "J1") (pin "PWR") (pinfunction "PWR_PWR") (pintype "bidirectional"))
      (node (ref "JP1") (pin "4") (pinfunction "4_4") (pintype "passive"))
    )
    (net (code "44") (name "Net-(JP1-Pad1)") (class "Default")
      (node (ref "JP1") (pin "1") (pinfunction "1_1") (pintype "passive"))
      (node (ref "POWER-EXT") (pin "1") (pinfunction "1_1") (pintype "passive"))
    )
    (net (code "45") (name "Net-(RN1B-1)") (class "Default")
      (node (ref "JP2") (pin "3") (pinfunction "3_3") (pintype "passive"))
      (node (ref "RN1") (pin "2") (pinfunction "1_2") (pintype "passive"))
    )
    (net (code "46") (name "Net-(RN1C-1)") (class "Default")
      (node (ref "JP2") (pin "1") (pinfunction "1_1") (pintype "passive"))
      (node (ref "RN1") (pin "3") (pinfunction "1_3") (pintype "passive"))
    )
    (net (code "47") (name "Net-(RN3C-1)") (class "Default")
      (node (ref "JP6") (pin "2") (pinfunction "2_2") (pintype "passive"))
      (node (ref "RN3") (pin "3") (pinfunction "1_3") (pintype "passive"))
    )
    (net (code "48") (name "Net-(RN3D-1)") (class "Default")
      (node (ref "JP7") (pin "2") (pinfunction "2_2") (pintype "passive"))
      (node (ref "RN3") (pin "4") (pinfunction "1_4") (pintype "passive"))
    )
    (net (code "49") (name "Net-(RN4C-1)") (class "Default")
      (node (ref "JP9") (pin "2") (pinfunction "2_2") (pintype "passive"))
      (node (ref "RN4") (pin "3") (pinfunction "1_3") (pintype "passive"))
    )
    (net (code "50") (name "Net-(RN4D-1)") (class "Default")
      (node (ref "JP10") (pin "2") (pinfunction "2_2") (pintype "passive"))
      (node (ref "RN4") (pin "4") (pinfunction "1_4") (pintype "passive"))
    )
    (net (code "51") (name "Net-(RN5C-1)") (class "Default")
      (node (ref "JP12") (pin "2") (pinfunction "2_2") (pintype "passive"))
      (node (ref "RN5") (pin "3") (pinfunction "1_3") (pintype "passive"))
    )
    (net (code "52") (name "Net-(RN5D-1)") (class "Default")
      (node (ref "JP13") (pin "2") (pinfunction "2_2") (pintype "passive"))
      (node (ref "RN5") (pin "4") (pinfunction "1_4") (pintype "passive"))
    )
    (net (code "53") (name "Net-(RN6C-1)") (class "Default")
      (node (ref "JP15") (pin "2") (pinfunction "2_2") (pintype "passive"))
      (node (ref "RN6") (pin "3") (pinfunction "1_3") (pintype "passive"))
    )
    (net (code "54") (name "Net-(RN6D-1)") (class "Default")
      (node (ref "JP16") (pin "2") (pinfunction "2_2") (pintype "passive"))
      (node (ref "RN6") (pin "4") (pinfunction "1_4") (pintype "passive"))
    )
    (net (code "55") (name "Net-(RN7C-1)") (class "Default")
      (node (ref "JP18") (pin "2") (pinfunction "2_2") (pintype "passive"))
      (node (ref "RN7") (pin "3") (pinfunction "1_3") (pintype "passive"))
    )
    (net (code "56") (name "Net-(RN7D-1)") (class "Default")
      (node (ref "JP19") (pin "2") (pinfunction "2_2") (pintype "passive"))
      (node (ref "RN7") (pin "4") (pinfunction "1_4") (pintype "passive"))
    )
    (net (code "57") (name "Net-(RN8C-1)") (class "Default")
      (node (ref "JP21") (pin "2") (pinfunction "2_2") (pintype "passive"))
      (node (ref "RN8") (pin "3") (pinfunction "1_3") (pintype "passive"))
    )
    (net (code "58") (name "Net-(RN8D-1)") (class "Default")
      (node (ref "JP22") (pin "2") (pinfunction "2_2") (pintype "passive"))
      (node (ref "RN8") (pin "4") (pinfunction "1_4") (pintype "passive"))
    )
    (net (code "59") (name "Net-(RN9C-1)") (class "Default")
      (node (ref "JP24") (pin "2") (pinfunction "2_2") (pintype "passive"))
      (node (ref "RN9") (pin "3") (pinfunction "1_3") (pintype "passive"))
    )
    (net (code "60") (name "Net-(RN9D-1)") (class "Default")
      (node (ref "JP25") (pin "2") (pinfunction "2_2") (pintype "passive"))
      (node (ref "RN9") (pin "4") (pinfunction "1_4") (pintype "passive"))
    )
    (net (code "61") (name "Net-(RN10C-1)") (class "Default")
      (node (ref "JP27") (pin "2") (pinfunction "2_2") (pintype "passive"))
      (node (ref "RN10") (pin "3") (pinfunction "1_3") (pintype "passive"))
    )
    (net (code "62") (name "Net-(RN10D-1)") (class "Default")
      (node (ref "JP28") (pin "2") (pinfunction "2_2") (pintype "passive"))
      (node (ref "RN10") (pin "4") (pinfunction "1_4") (pintype "passive"))
    )
    (net (code "63") (name "Net-(T1-B)") (class "Default")
      (node (ref "JP29") (pin "2") (pinfunction "2_2") (pintype "passive"))
      (node (ref "T1") (pin "1") (pinfunction "C_1") (pintype "passive"))
      (node (ref "T1") (pin "2") (pinfunction "B_2") (pintype "passive"))
    )
    (net (code "64") (name "RST") (class "Default")
      (node (ref "IDC1") (pin "6") (pinfunction "6_6") (pintype "bidirectional"))
      (node (ref "IDC2") (pin "6") (pinfunction "6_6") (pintype "bidirectional"))
      (node (ref "JP5") (pin "1") (pinfunction "1_1") (pintype "passive"))
    )
    (net (code "65") (name "SCL") (class "Default")
      (node (ref "IC3") (pin "22") (pinfunction "SCL_22") (pintype "bidirectional"))
      (node (ref "IDC1") (pin "1") (pinfunction "1_1") (pintype "bidirectional"))
      (node (ref "IDC2") (pin "1") (pinfunction "1_1") (pintype "bidirectional"))
      (node (ref "JP2") (pin "4") (pinfunction "4_4") (pintype "passive"))
    )
    (net (code "66") (name "SCL0") (class "Default")
      (node (ref "IC3") (pin "5") (pinfunction "SC0_5") (pintype "bidirectional"))
      (node (ref "IC4") (pin "8") (pinfunction "SMCLK_8") (pintype "bidirectional"))
      (node (ref "RN3") (pin "1") (pinfunction "1_1") (pintype "passive"))
    )
    (net (code "67") (name "SCL1") (class "Default")
      (node (ref "IC3") (pin "7") (pinfunction "SC1_7") (pintype "bidirectional"))
      (node (ref "IC5") (pin "8") (pinfunction "SMCLK_8") (pintype "bidirectional"))
      (node (ref "RN4") (pin "1") (pinfunction "1_1") (pintype "passive"))
    )
    (net (code "68") (name "SCL2") (class "Default")
      (node (ref "IC3") (pin "9") (pinfunction "SC2_9") (pintype "bidirectional"))
      (node (ref "IC6") (pin "8") (pinfunction "SMCLK_8") (pintype "bidirectional"))
      (node (ref "RN5") (pin "1") (pinfunction "1_1") (pintype "passive"))
    )
    (net (code "69") (name "SCL3") (class "Default")
      (node (ref "IC3") (pin "11") (pinfunction "SC3_11") (pintype "bidirectional"))
      (node (ref "IC7") (pin "8") (pinfunction "SMCLK_8") (pintype "bidirectional"))
      (node (ref "RN6") (pin "1") (pinfunction "1_1") (pintype "passive"))
    )
    (net (code "70") (name "SCL4") (class "Default")
      (node (ref "IC3") (pin "14") (pinfunction "SC4_14") (pintype "bidirectional"))
      (node (ref "IC8") (pin "8") (pinfunction "SMCLK_8") (pintype "bidirectional"))
      (node (ref "RN7") (pin "1") (pinfunction "1_1") (pintype "passive"))
    )
    (net (code "71") (name "SCL5") (class "Default")
      (node (ref "IC3") (pin "16") (pinfunction "SC5_16") (pintype "bidirectional"))
      (node (ref "IC9") (pin "8") (pinfunction "SMCLK_8") (pintype "bidirectional"))
      (node (ref "RN8") (pin "1") (pinfunction "1_1") (pintype "passive"))
    )
    (net (code "72") (name "SCL6") (class "Default")
      (node (ref "IC10") (pin "8") (pinfunction "SMCLK_8") (pintype "bidirectional"))
      (node (ref "IC3") (pin "18") (pinfunction "SC6_18") (pintype "bidirectional"))
      (node (ref "RN9") (pin "1") (pinfunction "1_1") (pintype "passive"))
    )
    (net (code "73") (name "SCL7") (class "Default")
      (node (ref "IC11") (pin "8") (pinfunction "SMCLK_8") (pintype "bidirectional"))
      (node (ref "IC3") (pin "20") (pinfunction "SC7_20") (pintype "bidirectional"))
      (node (ref "RN10") (pin "1") (pinfunction "1_1") (pintype "passive"))
    )
    (net (code "74") (name "SDA") (class "Default")
      (node (ref "IC3") (pin "23") (pinfunction "SDA_23") (pintype "bidirectional"))
      (node (ref "IDC1") (pin "2") (pinfunction "2_2") (pintype "bidirectional"))
      (node (ref "IDC2") (pin "2") (pinfunction "2_2") (pintype "bidirectional"))
      (node (ref "JP2") (pin "2") (pinfunction "2_2") (pintype "passive"))
    )
    (net (code "75") (name "SDA0") (class "Default")
      (node (ref "IC3") (pin "4") (pinfunction "SD0_4") (pintype "bidirectional"))
      (node (ref "IC4") (pin "7") (pinfunction "SMDATA_7") (pintype "bidirectional"))
      (node (ref "RN3") (pin "2") (pinfunction "1_2") (pintype "passive"))
    )
    (net (code "76") (name "SDA1") (class "Default")
      (node (ref "IC3") (pin "6") (pinfunction "SD1_6") (pintype "bidirectional"))
      (node (ref "IC5") (pin "7") (pinfunction "SMDATA_7") (pintype "bidirectional"))
      (node (ref "RN4") (pin "2") (pinfunction "1_2") (pintype "passive"))
    )
    (net (code "77") (name "SDA2") (class "Default")
      (node (ref "IC3") (pin "8") (pinfunction "SD2_8") (pintype "bidirectional"))
      (node (ref "IC6") (pin "7") (pinfunction "SMDATA_7") (pintype "bidirectional"))
      (node (ref "RN5") (pin "2") (pinfunction "1_2") (pintype "passive"))
    )
    (net (code "78") (name "SDA3") (class "Default")
      (node (ref "IC3") (pin "10") (pinfunction "SD3_10") (pintype "bidirectional"))
      (node (ref "IC7") (pin "7") (pinfunction "SMDATA_7") (pintype "bidirectional"))
      (node (ref "RN6") (pin "2") (pinfunction "1_2") (pintype "passive"))
    )
    (net (code "79") (name "SDA4") (class "Default")
      (node (ref "IC3") (pin "13") (pinfunction "SD4_13") (pintype "bidirectional"))
      (node (ref "IC8") (pin "7") (pinfunction "SMDATA_7") (pintype "bidirectional"))
      (node (ref "RN7") (pin "2") (pinfunction "1_2") (pintype "passive"))
    )
    (net (code "80") (name "SDA5") (class "Default")
      (node (ref "IC3") (pin "15") (pinfunction "SD5_15") (pintype "bidirectional"))
      (node (ref "IC9") (pin "7") (pinfunction "SMDATA_7") (pintype "bidirectional"))
      (node (ref "RN8") (pin "2") (pinfunction "1_2") (pintype "passive"))
    )
    (net (code "81") (name "SDA6") (class "Default")
      (node (ref "IC10") (pin "7") (pinfunction "SMDATA_7") (pintype "bidirectional"))
      (node (ref "IC3") (pin "17") (pinfunction "SD6_17") (pintype "bidirectional"))
      (node (ref "RN9") (pin "2") (pinfunction "1_2") (pintype "passive"))
    )
    (net (code "82") (name "SDA7") (class "Default")
      (node (ref "IC11") (pin "7") (pinfunction "SMDATA_7") (pintype "bidirectional"))
      (node (ref "IC3") (pin "19") (pinfunction "SD7_19") (pintype "bidirectional"))
      (node (ref "RN10") (pin "2") (pinfunction "1_2") (pintype "passive"))
    )
    (net (code "83") (name "TACH0") (class "Default")
      (node (ref "IC4") (pin "6") (pinfunction "~{ALERT_}/_TACH_6") (pintype "bidirectional"))
      (node (ref "J2") (pin "A2") (pinfunction "A2_A2") (pintype "bidirectional"))
      (node (ref "JP6") (pin "1") (pinfunction "1_1") (pintype "passive"))
    )
    (net (code "84") (name "TACH1") (class "Default")
      (node (ref "IC5") (pin "6") (pinfunction "~{ALERT_}/_TACH_6") (pintype "bidirectional"))
      (node (ref "J2") (pin "E2") (pinfunction "E2_E2") (pintype "bidirectional"))
      (node (ref "JP9") (pin "1") (pinfunction "1_1") (pintype "passive"))
    )
    (net (code "85") (name "TACH2") (class "Default")
      (node (ref "IC6") (pin "6") (pinfunction "~{ALERT_}/_TACH_6") (pintype "bidirectional"))
      (node (ref "J2") (pin "B2") (pinfunction "B2_B2") (pintype "bidirectional"))
      (node (ref "JP12") (pin "1") (pinfunction "1_1") (pintype "passive"))
    )
    (net (code "86") (name "TACH3") (class "Default")
      (node (ref "IC7") (pin "6") (pinfunction "~{ALERT_}/_TACH_6") (pintype "bidirectional"))
      (node (ref "J2") (pin "F2") (pinfunction "F2_F2") (pintype "bidirectional"))
      (node (ref "JP15") (pin "1") (pinfunction "1_1") (pintype "passive"))
    )
    (net (code "87") (name "TACH4") (class "Default")
      (node (ref "IC8") (pin "6") (pinfunction "~{ALERT_}/_TACH_6") (pintype "bidirectional"))
      (node (ref "J2") (pin "C2") (pinfunction "C2_C2") (pintype "bidirectional"))
      (node (ref "JP18") (pin "1") (pinfunction "1_1") (pintype "passive"))
    )
    (net (code "88") (name "TACH5") (class "Default")
      (node (ref "IC9") (pin "6") (pinfunction "~{ALERT_}/_TACH_6") (pintype "bidirectional"))
      (node (ref "J2") (pin "G2") (pinfunction "G2_G2") (pintype "bidirectional"))
      (node (ref "JP21") (pin "1") (pinfunction "1_1") (pintype "passive"))
    )
    (net (code "89") (name "TACH6") (class "Default")
      (node (ref "IC10") (pin "6") (pinfunction "~{ALERT_}/_TACH_6") (pintype "bidirectional"))
      (node (ref "J2") (pin "D2") (pinfunction "D2_D2") (pintype "bidirectional"))
      (node (ref "J3") (pin "4") (pinfunction "4_4") (pintype "bidirectional"))
      (node (ref "JP24") (pin "1") (pinfunction "1_1") (pintype "passive"))
    )
    (net (code "90") (name "TACH7") (class "Default")
      (node (ref "IC11") (pin "6") (pinfunction "~{ALERT_}/_TACH_6") (pintype "bidirectional"))
      (node (ref "J2") (pin "H2") (pinfunction "H2_H2") (pintype "bidirectional"))
      (node (ref "JP27") (pin "1") (pinfunction "1_1") (pintype "passive"))
    )
    (net (code "91") (name "VCC") (class "Default")
      (node (ref "C10") (pin "1") (pinfunction "1_1") (pintype "passive"))
      (node (ref "C11") (pin "1") (pinfunction "1_1") (pintype "passive"))
      (node (ref "C12") (pin "1") (pinfunction "1_1") (pintype "passive"))
      (node (ref "C13") (pin "1") (pinfunction "1_1") (pintype "passive"))
      (node (ref "C14") (pin "1") (pinfunction "1_1") (pintype "passive"))
      (node (ref "C2") (pin "1") (pinfunction "+_1") (pintype "bidirectional"))
      (node (ref "C6") (pin "1") (pinfunction "1_1") (pintype "passive"))
      (node (ref "C7") (pin "1") (pinfunction "1_1") (pintype "passive"))
      (node (ref "C8") (pin "1") (pinfunction "1_1") (pintype "passive"))
      (node (ref "C9") (pin "1") (pinfunction "1_1") (pintype "passive"))
      (node (ref "IC10") (pin "1") (pinfunction "VDD_1") (pintype "power_in"))
      (node (ref "IC11") (pin "1") (pinfunction "VDD_1") (pintype "power_in"))
      (node (ref "IC2") (pin "4") (pinfunction "FEEDBACK_4") (pintype "bidirectional"))
      (node (ref "IC3") (pin "24") (pinfunction "VCC_24") (pintype "bidirectional"))
      (node (ref "IC4") (pin "1") (pinfunction "VDD_1") (pintype "power_in"))
      (node (ref "IC5") (pin "1") (pinfunction "VDD_1") (pintype "power_in"))
      (node (ref "IC6") (pin "1") (pinfunction "VDD_1") (pintype "power_in"))
      (node (ref "IC7") (pin "1") (pinfunction "VDD_1") (pintype "power_in"))
      (node (ref "IC8") (pin "1") (pinfunction "VDD_1") (pintype "power_in"))
      (node (ref "IC9") (pin "1") (pinfunction "VDD_1") (pintype "power_in"))
      (node (ref "JP3") (pin "2") (pinfunction "2_2") (pintype "passive"))
      (node (ref "JP3") (pin "4") (pinfunction "4_4") (pintype "passive"))
      (node (ref "JP3") (pin "6") (pinfunction "6_6") (pintype "passive"))
      (node (ref "L1") (pin "2") (pinfunction "2_2") (pintype "bidirectional"))
      (node (ref "RN1") (pin "5") (pinfunction "2_5") (pintype "passive"))
      (node (ref "RN1") (pin "6") (pinfunction "2_6") (pintype "passive"))
      (node (ref "RN1") (pin "7") (pinfunction "2_7") (pintype "passive"))
      (node (ref "RN10") (pin "5") (pinfunction "2_5") (pintype "passive"))
      (node (ref "RN10") (pin "6") (pinfunction "2_6") (pintype "passive"))
      (node (ref "RN10") (pin "7") (pinfunction "2_7") (pintype "passive"))
      (node (ref "RN10") (pin "8") (pinfunction "2_8") (pintype "passive"))
      (node (ref "RN3") (pin "5") (pinfunction "2_5") (pintype "passive"))
      (node (ref "RN3") (pin "6") (pinfunction "2_6") (pintype "passive"))
      (node (ref "RN3") (pin "7") (pinfunction "2_7") (pintype "passive"))
      (node (ref "RN3") (pin "8") (pinfunction "2_8") (pintype "passive"))
      (node (ref "RN4") (pin "5") (pinfunction "2_5") (pintype "passive"))
      (node (ref "RN4") (pin "6") (pinfunction "2_6") (pintype "passive"))
      (node (ref "RN4") (pin "7") (pinfunction "2_7") (pintype "passive"))
      (node (ref "RN4") (pin "8") (pinfunction "2_8") (pintype "passive"))
      (node (ref "RN5") (pin "5") (pinfunction "2_5") (pintype "passive"))
      (node (ref "RN5") (pin "6") (pinfunction "2_6") (pintype "passive"))
      (node (ref "RN5") (pin "7") (pinfunction "2_7") (pintype "passive"))
      (node (ref "RN5") (pin "8") (pinfunction "2_8") (pintype "passive"))
      (node (ref "RN6") (pin "5") (pinfunction "2_5") (pintype "passive"))
      (node (ref "RN6") (pin "6") (pinfunction "2_6") (pintype "passive"))
      (node (ref "RN6") (pin "7") (pinfunction "2_7") (pintype "passive"))
      (node (ref "RN6") (pin "8") (pinfunction "2_8") (pintype "passive"))
      (node (ref "RN7") (pin "5") (pinfunction "2_5") (pintype "passive"))
      (node (ref "RN7") (pin "6") (pinfunction "2_6") (pintype "passive"))
      (node (ref "RN7") (pin "7") (pinfunction "2_7") (pintype "passive"))
      (node (ref "RN7") (pin "8") (pinfunction "2_8") (pintype "passive"))
      (node (ref "RN8") (pin "5") (pinfunction "2_5") (pintype "passive"))
      (node (ref "RN8") (pin "6") (pinfunction "2_6") (pintype "passive"))
      (node (ref "RN8") (pin "7") (pinfunction "2_7") (pintype "passive"))
      (node (ref "RN8") (pin "8") (pinfunction "2_8") (pintype "passive"))
      (node (ref "RN9") (pin "5") (pinfunction "2_5") (pintype "passive"))
      (node (ref "RN9") (pin "6") (pinfunction "2_6") (pintype "passive"))
      (node (ref "RN9") (pin "7") (pinfunction "2_7") (pintype "passive"))
      (node (ref "RN9") (pin "8") (pinfunction "2_8") (pintype "passive"))
    )
    (net (code "92") (name "VDD") (class "Default")
      (node (ref "C1") (pin "1") (pinfunction "+_1") (pintype "bidirectional"))
      (node (ref "C3") (pin "1") (pinfunction "+_1") (pintype "bidirectional"))
      (node (ref "IC1") (pin "1") (pinfunction "VIN_1") (pintype "input"))
      (node (ref "IC2") (pin "1") (pinfunction "VIN_1") (pintype "input"))
      (node (ref "JP1") (pin "3") (pinfunction "3_3") (pintype "passive"))
      (node (ref "JP11") (pin "3") (pinfunction "3_3") (pintype "passive"))
      (node (ref "JP14") (pin "3") (pinfunction "3_3") (pintype "passive"))
      (node (ref "JP17") (pin "3") (pinfunction "3_3") (pintype "passive"))
      (node (ref "JP20") (pin "3") (pinfunction "3_3") (pintype "passive"))
      (node (ref "JP23") (pin "3") (pinfunction "3_3") (pintype "passive"))
      (node (ref "JP26") (pin "3") (pinfunction "3_3") (pintype "passive"))
      (node (ref "JP4") (pin "3") (pinfunction "3_3") (pintype "passive"))
      (node (ref "JP8") (pin "3") (pinfunction "3_3") (pintype "passive"))
    )
    (net (code "93") (name "unconnected-(JP1-Pad2)") (class "Default")
      (node (ref "JP1") (pin "2") (pinfunction "2_2") (pintype "passive"))
    )
    (net (code "94") (name "unconnected-(JP1-Pad6)") (class "Default")
      (node (ref "JP1") (pin "6") (pinfunction "6_6") (pintype "passive"))
    )
    (net (code "95") (name "unconnected-(JP4-Pad4)") (class "Default")
      (node (ref "JP4") (pin "4") (pinfunction "4_4") (pintype "passive"))
    )
    (net (code "96") (name "unconnected-(JP8-Pad4)") (class "Default")
      (node (ref "JP8") (pin "4") (pinfunction "4_4") (pintype "passive"))
    )
    (net (code "97") (name "unconnected-(JP11-Pad4)") (class "Default")
      (node (ref "JP11") (pin "4") (pinfunction "4_4") (pintype "passive"))
    )
    (net (code "98") (name "unconnected-(JP14-Pad4)") (class "Default")
      (node (ref "JP14") (pin "4") (pinfunction "4_4") (pintype "passive"))
    )
    (net (code "99") (name "unconnected-(JP17-Pad4)") (class "Default")
      (node (ref "JP17") (pin "4") (pinfunction "4_4") (pintype "passive"))
    )
    (net (code "100") (name "unconnected-(JP20-Pad4)") (class "Default")
      (node (ref "JP20") (pin "4") (pinfunction "4_4") (pintype "passive"))
    )
    (net (code "101") (name "unconnected-(JP23-Pad4)") (class "Default")
      (node (ref "JP23") (pin "4") (pinfunction "4_4") (pintype "passive"))
    )
    (net (code "102") (name "unconnected-(JP26-Pad4)") (class "Default")
      (node (ref "JP26") (pin "4") (pinfunction "4_4") (pintype "passive"))
    )
    (net (code "103") (name "unconnected-(RN1-Pad1)") (class "Default")
      (node (ref "RN1") (pin "1") (pinfunction "1_1") (pintype "passive"))
    )
    (net (code "104") (name "unconnected-(RN1A-2-Pad8)") (class "Default")
      (node (ref "RN1") (pin "8") (pinfunction "2_8") (pintype "passive"))
    )
    (net (code "105") (name "unconnected-(RN2-Pad1)") (class "Default")
      (node (ref "RN2") (pin "1") (pinfunction "1_1") (pintype "passive"))
    )
    (net (code "106") (name "unconnected-(RN2A-2-Pad8)") (class "Default")
      (node (ref "RN2") (pin "8") (pinfunction "2_8") (pintype "passive"))
    )
  )
)
